# microzed_sd_v0_5_r1_1_f6faa5a5.net
KiCad netlist of a schematic drawn in EAGLE
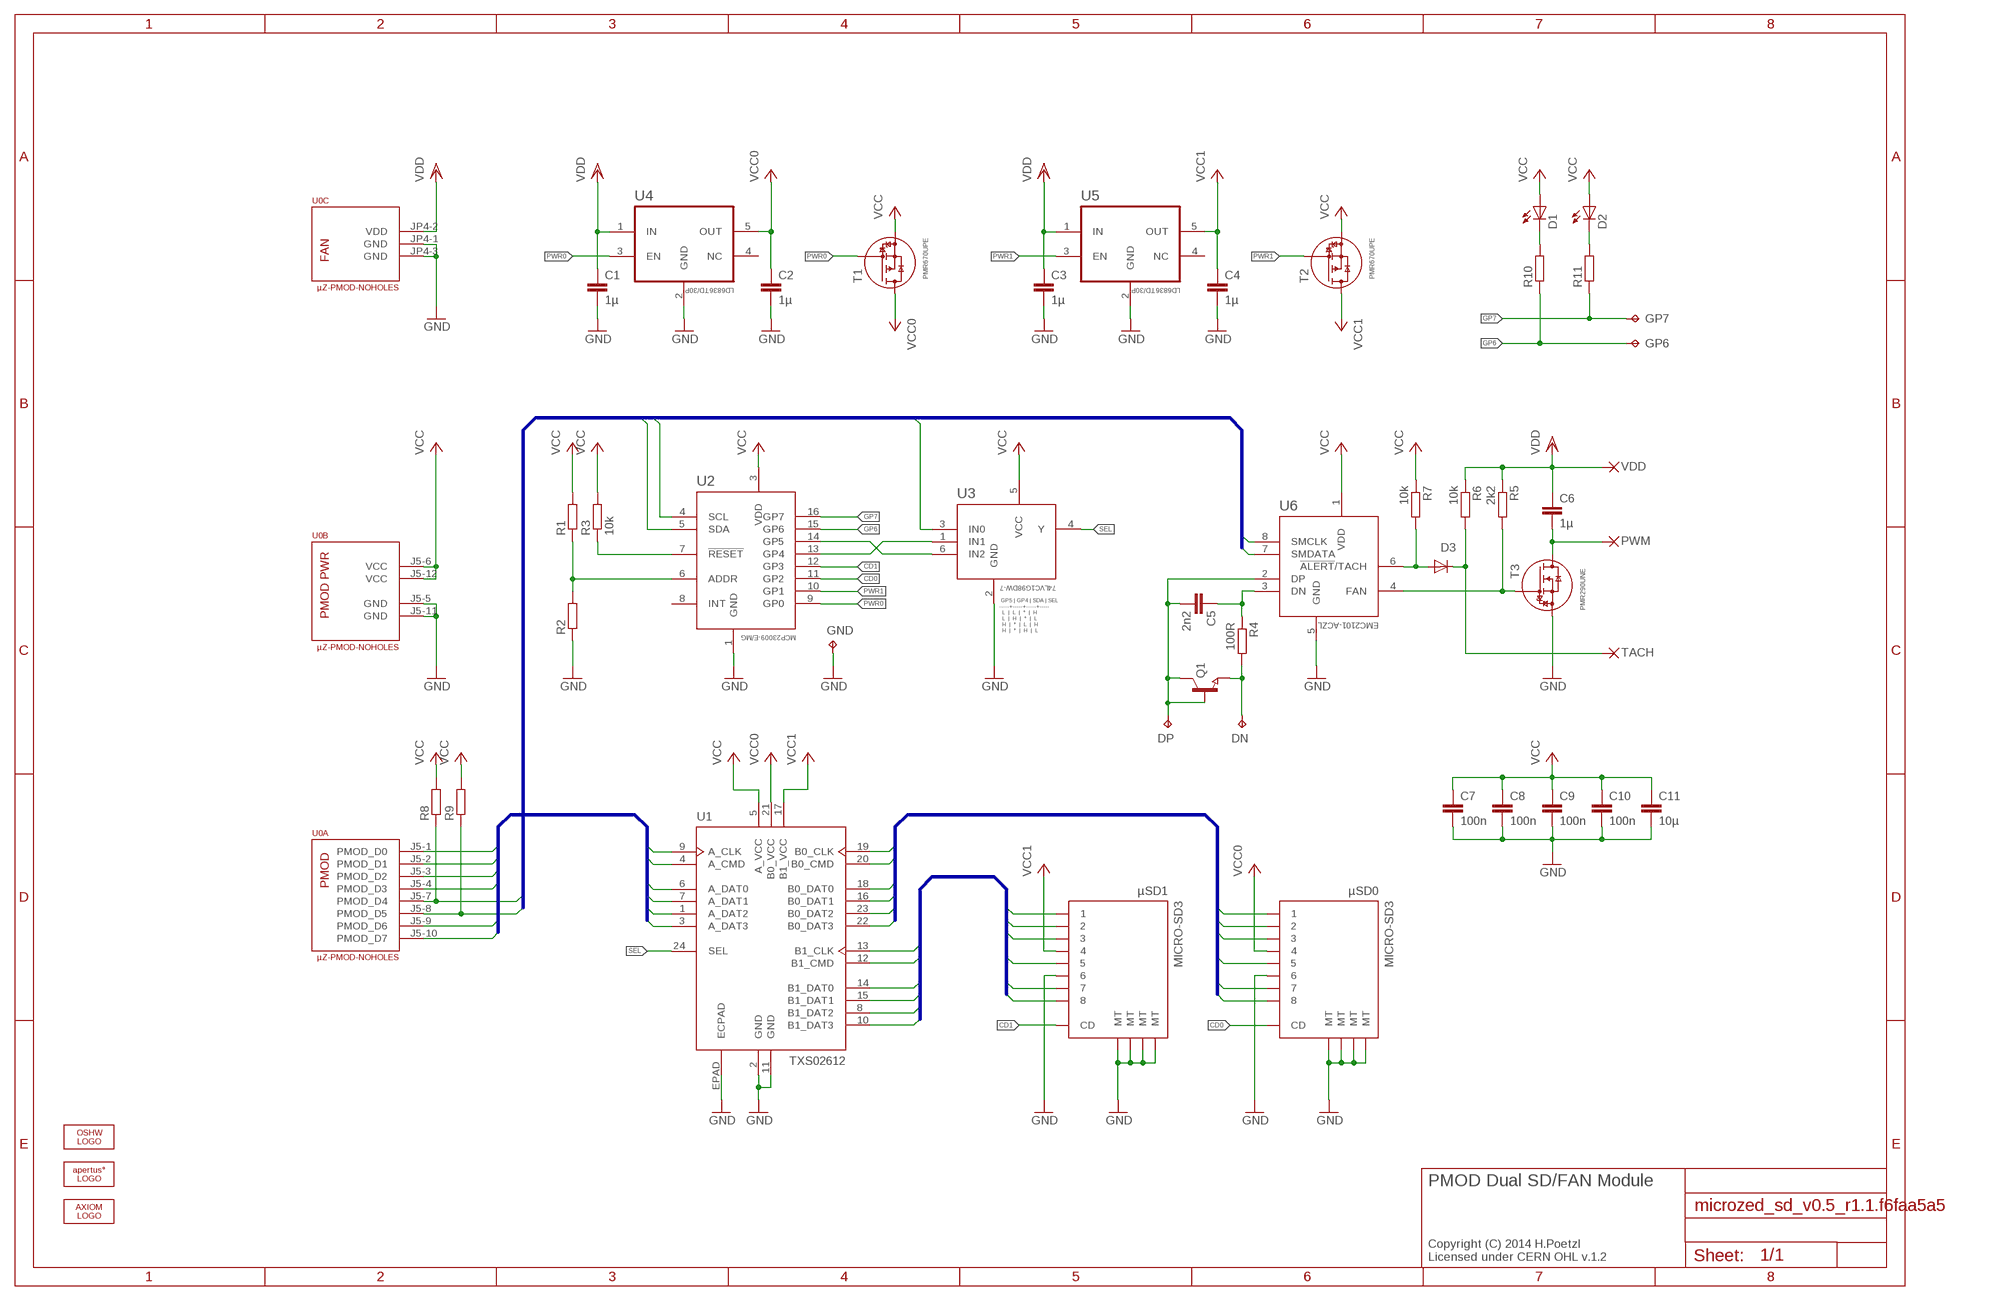
[diagram p0: schematic, sheet 1]

(export (version "E")
  (design (tool "Eeschema 10.0.6"))
  (components
    (comp (ref "C1")
      (value "1µ")
      (footprint "eagle-import:C0402K")
      (libsource (lib "eagle-import") (part "C-EUC0402K"))
    )
    (comp (ref "C2")
      (value "1µ")
      (footprint "eagle-import:C0402K")
      (libsource (lib "eagle-import") (part "C-EUC0402K"))
    )
    (comp (ref "C3")
      (value "1µ")
      (footprint "eagle-import:C0402K")
      (libsource (lib "eagle-import") (part "C-EUC0402K"))
    )
    (comp (ref "C4")
      (value "1µ")
      (footprint "eagle-import:C0402K")
      (libsource (lib "eagle-import") (part "C-EUC0402K"))
    )
    (comp (ref "C5")
      (value "2n2")
      (footprint "eagle-import:C0402K")
      (libsource (lib "eagle-import") (part "C-EUC0402K"))
    )
    (comp (ref "C6")
      (value "1µ")
      (footprint "eagle-import:C0402K")
      (libsource (lib "eagle-import") (part "C-EUC0402K"))
    )
    (comp (ref "C7")
      (value "100n")
      (footprint "eagle-import:C0402K")
      (libsource (lib "eagle-import") (part "C-EUC0402K"))
    )
    (comp (ref "C8")
      (value "100n")
      (footprint "eagle-import:C0402K")
      (libsource (lib "eagle-import") (part "C-EUC0402K"))
    )
    (comp (ref "C9")
      (value "100n")
      (footprint "eagle-import:C0402K")
      (libsource (lib "eagle-import") (part "C-EUC0402K"))
    )
    (comp (ref "C10")
      (value "100n")
      (footprint "eagle-import:C0402K")
      (libsource (lib "eagle-import") (part "C-EUC0402K"))
    )
    (comp (ref "C11")
      (value "10µ")
      (footprint "eagle-import:C0603K")
      (libsource (lib "eagle-import") (part "C-EUC0603K"))
    )
    (comp (ref "D1")
      (value "LEDCHIPLED_0603")
      (footprint "eagle-import:CHIPLED_0603")
      (libsource (lib "eagle-import") (part "LEDCHIPLED_0603"))
    )
    (comp (ref "D2")
      (value "LEDCHIPLED_0603")
      (footprint "eagle-import:CHIPLED_0603")
      (libsource (lib "eagle-import") (part "LEDCHIPLED_0603"))
    )
    (comp (ref "D3")
      (value "DIODE-MICROMELF-W")
      (footprint "eagle-import:MICROMELF-W")
      (libsource (lib "eagle-import") (part "DIODE-MICROMELF-W"))
    )
    (comp (ref "DN")
      (value "TPTP20R")
      (footprint "eagle-import:TP20R")
      (libsource (lib "eagle-import") (part "TPTP20R"))
    )
    (comp (ref "DP")
      (value "TPTP20R")
      (footprint "eagle-import:TP20R")
      (libsource (lib "eagle-import") (part "TPTP20R"))
    )
    (comp (ref "GND")
      (value "TPTP20R")
      (footprint "eagle-import:TP20R")
      (libsource (lib "eagle-import") (part "TPTP20R"))
    )
    (comp (ref "GP6")
      (value "TPTP20R")
      (footprint "eagle-import:TP20R")
      (libsource (lib "eagle-import") (part "TPTP20R"))
    )
    (comp (ref "GP7")
      (value "TPTP20R")
      (footprint "eagle-import:TP20R")
      (libsource (lib "eagle-import") (part "TPTP20R"))
    )
    (comp (ref "LOGO1")
      (value "OSHW_LOGO_FILLX0100-NT")
      (footprint "eagle-import:OSHW_FILLX100_NOTEXT")
      (libsource (lib "eagle-import") (part "OSHW_LOGO_FILLX0100-NT"))
    )
    (comp (ref "PWM")
      (value "WIREPAD1,85/1,0_SQ")
      (footprint "eagle-import:1,85_1,0_SQ")
      (libsource (lib "eagle-import") (part "WIREPAD1,85/1,0_SQ"))
    )
    (comp (ref "Q1")
      (value "NPN-TRANSISTOR_SOT23")
      (footprint "eagle-import:SOT23")
      (libsource (lib "eagle-import") (part "NPN-TRANSISTOR_SOT23"))
    )
    (comp (ref "R1")
      (value "R-EU_R0402")
      (footprint "eagle-import:R0402")
      (libsource (lib "eagle-import") (part "R-EU_R0402"))
    )
    (comp (ref "R2")
      (value "R-EU_R0402")
      (footprint "eagle-import:R0402")
      (libsource (lib "eagle-import") (part "R-EU_R0402"))
    )
    (comp (ref "R3")
      (value "10k")
      (footprint "eagle-import:R0402")
      (libsource (lib "eagle-import") (part "R-EU_R0402"))
    )
    (comp (ref "R4")
      (value "100R")
      (footprint "eagle-import:R0402")
      (libsource (lib "eagle-import") (part "R-EU_R0402"))
    )
    (comp (ref "R5")
      (value "2k2")
      (footprint "eagle-import:R0402")
      (libsource (lib "eagle-import") (part "R-EU_R0402"))
    )
    (comp (ref "R6")
      (value "10k")
      (footprint "eagle-import:R0402")
      (libsource (lib "eagle-import") (part "R-EU_R0402"))
    )
    (comp (ref "R7")
      (value "10k")
      (footprint "eagle-import:R0402")
      (libsource (lib "eagle-import") (part "R-EU_R0402"))
    )
    (comp (ref "R8")
      (value "R-EU_R0402")
      (footprint "eagle-import:R0402")
      (libsource (lib "eagle-import") (part "R-EU_R0402"))
    )
    (comp (ref "R9")
      (value "R-EU_R0402")
      (footprint "eagle-import:R0402")
      (libsource (lib "eagle-import") (part "R-EU_R0402"))
    )
    (comp (ref "R10")
      (value "R-EU_R0402")
      (footprint "eagle-import:R0402")
      (libsource (lib "eagle-import") (part "R-EU_R0402"))
    )
    (comp (ref "R11")
      (value "R-EU_R0402")
      (footprint "eagle-import:R0402")
      (libsource (lib "eagle-import") (part "R-EU_R0402"))
    )
    (comp (ref "T1")
      (value "PMR670UPE")
      (footprint "eagle-import:SOT416")
      (libsource (lib "eagle-import") (part "PMR670UPE"))
    )
    (comp (ref "T2")
      (value "PMR670UPE")
      (footprint "eagle-import:SOT416")
      (libsource (lib "eagle-import") (part "PMR670UPE"))
    )
    (comp (ref "T3")
      (value "PMR290UNE")
      (footprint "eagle-import:SOT416")
      (libsource (lib "eagle-import") (part "PMR290UNE"))
    )
    (comp (ref "TACH")
      (value "WIREPAD1,85/1,0")
      (footprint "eagle-import:1,85_1,0")
      (libsource (lib "eagle-import") (part "WIREPAD1,85/1,0"))
    )
    (comp (ref "U$1")
      (value "APERTUS_LOGO334X100")
      (footprint "eagle-import:APERTUS_LOGO_334X100")
      (libsource (lib "eagle-import") (part "APERTUS_LOGO334X100"))
    )
    (comp (ref "U$13")
      (value "AXIOM_LOGO525X80")
      (footprint "eagle-import:AXIOM_LOGO_525X80")
      (libsource (lib "eagle-import") (part "AXIOM_LOGO525X80"))
    )
    (comp (ref "U0")
      (value "µZ-PMOD-NOHOLES")
      (footprint "eagle-import:µZ-TOP-NOHOLES")
      (libsource (lib "eagle-import") (part "µZ-PMOD-NOHOLES"))
    )
    (comp (ref "U1")
      (value "TXS02612")
      (footprint "eagle-import:S-PWQFN-N24")
      (libsource (lib "eagle-import") (part "TXS02612"))
    )
    (comp (ref "U2")
      (value "MCP23009-E/MG")
      (footprint "eagle-import:QFN50P300X300X80-17N")
      (libsource (lib "eagle-import") (part "MCP23009-E/MG"))
    )
    (comp (ref "U3")
      (value "74LVC1G98DW-7")
      (footprint "eagle-import:SOT65P210X110-6N")
      (libsource (lib "eagle-import") (part "74LVC1G98DW-7"))
    )
    (comp (ref "U4")
      (value "LD6836TD/30P")
      (footprint "eagle-import:SOT95P275X110-5N")
      (libsource (lib "eagle-import") (part "LD6836TD/30P"))
    )
    (comp (ref "U5")
      (value "LD6836TD/30P")
      (footprint "eagle-import:SOT95P275X110-5N")
      (libsource (lib "eagle-import") (part "LD6836TD/30P"))
    )
    (comp (ref "U6")
      (value "EMC2101-ACZL")
      (footprint "eagle-import:SOP65P490X110-8N")
      (fields (field (name "MPN") "EMC2101-ACZL-TR "))
      (libsource (lib "eagle-import") (part "EMC2101-ACZL"))
    )
    (comp (ref "VDD")
      (value "WIREPAD1,85/1,0")
      (footprint "eagle-import:1,85_1,0")
      (libsource (lib "eagle-import") (part "WIREPAD1,85/1,0"))
    )
    (comp (ref "µSD0")
      (value "MICRO-SD3")
      (footprint "eagle-import:TF-MICRO-SD_PP3")
      (libsource (lib "eagle-import") (part "MICRO-SD3"))
    )
    (comp (ref "µSD1")
      (value "MICRO-SD3")
      (footprint "eagle-import:TF-MICRO-SD_PP3")
      (libsource (lib "eagle-import") (part "MICRO-SD3"))
    )
  )
  (nets
    (net (code "1") (name "/A_CLK") (class "Default")
      (node (ref "U0") (pin "J5-4") (pinfunction "PMOD_D3_J5-4") (pintype "bidirectional"))
      (node (ref "U1") (pin "9") (pinfunction "A_CLK_9") (pintype "input"))
    )
    (net (code "2") (name "/A_CMD") (class "Default")
      (node (ref "U0") (pin "J5-3") (pinfunction "PMOD_D2_J5-3") (pintype "bidirectional"))
      (node (ref "U1") (pin "4") (pinfunction "A_CMD_4") (pintype "bidirectional"))
    )
    (net (code "3") (name "/A_DAT0") (class "Default")
      (node (ref "U0") (pin "J5-2") (pinfunction "PMOD_D1_J5-2") (pintype "bidirectional"))
      (node (ref "U1") (pin "6") (pinfunction "A_DAT0_6") (pintype "bidirectional"))
    )
    (net (code "4") (name "/A_DAT1") (class "Default")
      (node (ref "U0") (pin "J5-1") (pinfunction "PMOD_D0_J5-1") (pintype "bidirectional"))
      (node (ref "U1") (pin "7") (pinfunction "A_DAT1_7") (pintype "bidirectional"))
    )
    (net (code "5") (name "/A_DAT2") (class "Default")
      (node (ref "U0") (pin "J5-9") (pinfunction "PMOD_D6_J5-9") (pintype "bidirectional"))
      (node (ref "U1") (pin "1") (pinfunction "A_DAT2_1") (pintype "bidirectional"))
    )
    (net (code "6") (name "/A_DAT3") (class "Default")
      (node (ref "U0") (pin "J5-10") (pinfunction "PMOD_D7_J5-10") (pintype "bidirectional"))
      (node (ref "U1") (pin "3") (pinfunction "A_DAT3_3") (pintype "bidirectional"))
    )
    (net (code "7") (name "/B0_CLK") (class "Default")
      (node (ref "U1") (pin "19") (pinfunction "B0_CLK_19") (pintype "output"))
      (node (ref "µSD0") (pin "5") (pinfunction "5_5") (pintype "bidirectional"))
    )
    (net (code "8") (name "/B0_CMD") (class "Default")
      (node (ref "U1") (pin "20") (pinfunction "B0_CMD_20") (pintype "bidirectional"))
      (node (ref "µSD0") (pin "3") (pinfunction "3_3") (pintype "bidirectional"))
    )
    (net (code "9") (name "/B0_DAT0") (class "Default")
      (node (ref "U1") (pin "18") (pinfunction "B0_DAT0_18") (pintype "bidirectional"))
      (node (ref "µSD0") (pin "7") (pinfunction "7_7") (pintype "bidirectional"))
    )
    (net (code "10") (name "/B0_DAT1") (class "Default")
      (node (ref "U1") (pin "16") (pinfunction "B0_DAT1_16") (pintype "bidirectional"))
      (node (ref "µSD0") (pin "8") (pinfunction "8_8") (pintype "bidirectional"))
    )
    (net (code "11") (name "/B0_DAT2") (class "Default")
      (node (ref "U1") (pin "23") (pinfunction "B0_DAT2_23") (pintype "bidirectional"))
      (node (ref "µSD0") (pin "1") (pinfunction "1_1") (pintype "bidirectional"))
    )
    (net (code "12") (name "/B0_DAT3") (class "Default")
      (node (ref "U1") (pin "22") (pinfunction "B0_DAT3_22") (pintype "bidirectional"))
      (node (ref "µSD0") (pin "2") (pinfunction "2_2") (pintype "bidirectional"))
    )
    (net (code "13") (name "/B1_CLK") (class "Default")
      (node (ref "U1") (pin "13") (pinfunction "B1_CLK_13") (pintype "output"))
      (node (ref "µSD1") (pin "5") (pinfunction "5_5") (pintype "bidirectional"))
    )
    (net (code "14") (name "/B1_CMD") (class "Default")
      (node (ref "U1") (pin "12") (pinfunction "B1_CMD_12") (pintype "bidirectional"))
      (node (ref "µSD1") (pin "3") (pinfunction "3_3") (pintype "bidirectional"))
    )
    (net (code "15") (name "/B1_DAT0") (class "Default")
      (node (ref "U1") (pin "14") (pinfunction "B1_DAT0_14") (pintype "bidirectional"))
      (node (ref "µSD1") (pin "7") (pinfunction "7_7") (pintype "bidirectional"))
    )
    (net (code "16") (name "/B1_DAT1") (class "Default")
      (node (ref "U1") (pin "15") (pinfunction "B1_DAT1_15") (pintype "bidirectional"))
      (node (ref "µSD1") (pin "8") (pinfunction "8_8") (pintype "bidirectional"))
    )
    (net (code "17") (name "/B1_DAT2") (class "Default")
      (node (ref "U1") (pin "8") (pinfunction "B1_DAT2_8") (pintype "bidirectional"))
      (node (ref "µSD1") (pin "1") (pinfunction "1_1") (pintype "bidirectional"))
    )
    (net (code "18") (name "/B1_DAT3") (class "Default")
      (node (ref "U1") (pin "10") (pinfunction "B1_DAT3_10") (pintype "bidirectional"))
      (node (ref "µSD1") (pin "2") (pinfunction "2_2") (pintype "bidirectional"))
    )
    (net (code "19") (name "/SCL") (class "Default")
      (node (ref "R8") (pin "1") (pinfunction "1_1") (pintype "passive"))
      (node (ref "U0") (pin "J5-7") (pinfunction "PMOD_D4_J5-7") (pintype "bidirectional"))
      (node (ref "U2") (pin "4") (pinfunction "SCL_4") (pintype "input"))
      (node (ref "U6") (pin "8") (pinfunction "SMCLK_8") (pintype "input"))
    )
    (net (code "20") (name "/SDA") (class "Default")
      (node (ref "R9") (pin "1") (pinfunction "1_1") (pintype "passive"))
      (node (ref "U0") (pin "J5-8") (pinfunction "PMOD_D5_J5-8") (pintype "bidirectional"))
      (node (ref "U2") (pin "5") (pinfunction "SDA_5") (pintype "bidirectional"))
      (node (ref "U3") (pin "3") (pinfunction "IN0_3") (pintype "input"))
      (node (ref "U6") (pin "7") (pinfunction "SMDATA_7") (pintype "bidirectional"))
    )
    (net (code "21") (name "CD0") (class "Default")
      (node (ref "U2") (pin "11") (pinfunction "GP2_11") (pintype "bidirectional"))
      (node (ref "µSD0") (pin "CD") (pinfunction "CD_CD") (pintype "bidirectional"))
    )
    (net (code "22") (name "CD1") (class "Default")
      (node (ref "U2") (pin "12") (pinfunction "GP3_12") (pintype "bidirectional"))
      (node (ref "µSD1") (pin "CD") (pinfunction "CD_CD") (pintype "bidirectional"))
    )
    (net (code "23") (name "GND") (class "Default")
      (node (ref "C1") (pin "2") (pinfunction "2_2") (pintype "passive"))
      (node (ref "C10") (pin "2") (pinfunction "2_2") (pintype "passive"))
      (node (ref "C11") (pin "2") (pinfunction "2_2") (pintype "passive"))
      (node (ref "C2") (pin "2") (pinfunction "2_2") (pintype "passive"))
      (node (ref "C3") (pin "2") (pinfunction "2_2") (pintype "passive"))
      (node (ref "C4") (pin "2") (pinfunction "2_2") (pintype "passive"))
      (node (ref "C7") (pin "2") (pinfunction "2_2") (pintype "passive"))
      (node (ref "C8") (pin "2") (pinfunction "2_2") (pintype "passive"))
      (node (ref "C9") (pin "2") (pinfunction "2_2") (pintype "passive"))
      (node (ref "GND") (pin "TP") (pinfunction "TP_TP") (pintype "input"))
      (node (ref "R2") (pin "1") (pinfunction "1_1") (pintype "passive"))
      (node (ref "T3") (pin "2") (pinfunction "S_2") (pintype "passive"))
      (node (ref "U0") (pin "J5-11") (pinfunction "GND_J5-11") (pintype "power_in"))
      (node (ref "U0") (pin "J5-5") (pinfunction "GND_J5-5") (pintype "power_in"))
      (node (ref "U0") (pin "JP4-1") (pinfunction "GND_JP4-1") (pintype "power_in"))
      (node (ref "U0") (pin "JP4-3") (pinfunction "GND_JP4-3") (pintype "power_in"))
      (node (ref "U1") (pin "11") (pinfunction "GND_11") (pintype "power_in"))
      (node (ref "U1") (pin "2") (pinfunction "GND_2") (pintype "power_in"))
      (node (ref "U1") (pin "EPAD") (pinfunction "ECPAD_EPAD") (pintype "power_in"))
      (node (ref "U2") (pin "1") (pinfunction "GND_1") (pintype "power_in"))
      (node (ref "U3") (pin "2") (pinfunction "GND_2") (pintype "passive"))
      (node (ref "U4") (pin "2") (pinfunction "GND_2") (pintype "passive"))
      (node (ref "U5") (pin "2") (pinfunction "GND_2") (pintype "passive"))
      (node (ref "U6") (pin "5") (pinfunction "GND_5") (pintype "power_in"))
      (node (ref "µSD0") (pin "6") (pinfunction "6_6") (pintype "bidirectional"))
      (node (ref "µSD0") (pin "MT1") (pinfunction "MT_MT1") (pintype "power_in"))
      (node (ref "µSD0") (pin "MT2") (pinfunction "MT_MT2") (pintype "power_in"))
      (node (ref "µSD0") (pin "MT3") (pinfunction "MT_MT3") (pintype "power_in"))
      (node (ref "µSD0") (pin "MT4") (pinfunction "MT_MT4") (pintype "power_in"))
      (node (ref "µSD1") (pin "6") (pinfunction "6_6") (pintype "bidirectional"))
      (node (ref "µSD1") (pin "MT1") (pinfunction "MT_MT1") (pintype "power_in"))
      (node (ref "µSD1") (pin "MT2") (pinfunction "MT_MT2") (pintype "power_in"))
      (node (ref "µSD1") (pin "MT3") (pinfunction "MT_MT3") (pintype "power_in"))
      (node (ref "µSD1") (pin "MT4") (pinfunction "MT_MT4") (pintype "power_in"))
    )
    (net (code "24") (name "GP6") (class "Default")
      (node (ref "GP6") (pin "TP") (pinfunction "TP_TP") (pintype "input"))
      (node (ref "R10") (pin "1") (pinfunction "1_1") (pintype "passive"))
      (node (ref "U2") (pin "15") (pinfunction "GP6_15") (pintype "bidirectional"))
    )
    (net (code "25") (name "GP7") (class "Default")
      (node (ref "GP7") (pin "TP") (pinfunction "TP_TP") (pintype "input"))
      (node (ref "R11") (pin "1") (pinfunction "1_1") (pintype "passive"))
      (node (ref "U2") (pin "16") (pinfunction "GP7_16") (pintype "bidirectional"))
    )
    (net (code "26") (name "Net-(D1-PadC)") (class "Default")
      (node (ref "D1") (pin "C") (pinfunction "C_C") (pintype "passive"))
      (node (ref "R10") (pin "2") (pinfunction "2_2") (pintype "passive"))
    )
    (net (code "27") (name "Net-(D2-PadC)") (class "Default")
      (node (ref "D2") (pin "C") (pinfunction "C_C") (pintype "passive"))
      (node (ref "R11") (pin "2") (pinfunction "2_2") (pintype "passive"))
    )
    (net (code "28") (name "Net-(PWM-P)") (class "Default")
      (node (ref "C6") (pin "2") (pinfunction "2_2") (pintype "passive"))
      (node (ref "PWM") (pin "1") (pinfunction "P_1") (pintype "passive"))
      (node (ref "T3") (pin "3") (pinfunction "D_3") (pintype "passive"))
    )
    (net (code "29") (name "Net-(Q1-B)") (class "Default")
      (node (ref "C5") (pin "2") (pinfunction "2_2") (pintype "passive"))
      (node (ref "DP") (pin "TP") (pinfunction "TP_TP") (pintype "input"))
      (node (ref "Q1") (pin "1") (pinfunction "B_1") (pintype "passive"))
      (node (ref "Q1") (pin "3") (pinfunction "C_3") (pintype "passive"))
      (node (ref "U6") (pin "2") (pinfunction "DP_2") (pintype "passive"))
    )
    (net (code "30") (name "Net-(Q1-E)") (class "Default")
      (node (ref "DN") (pin "TP") (pinfunction "TP_TP") (pintype "input"))
      (node (ref "Q1") (pin "2") (pinfunction "E_2") (pintype "passive"))
      (node (ref "R4") (pin "2") (pinfunction "2_2") (pintype "passive"))
    )
    (net (code "31") (name "Net-(T3-G)") (class "Default")
      (node (ref "R5") (pin "2") (pinfunction "2_2") (pintype "passive"))
      (node (ref "T3") (pin "1") (pinfunction "G_1") (pintype "passive"))
      (node (ref "U6") (pin "4") (pinfunction "FAN_4") (pintype "output"))
    )
    (net (code "32") (name "Net-(TACH-P)") (class "Default")
      (node (ref "D3") (pin "C") (pinfunction "C_C") (pintype "passive"))
      (node (ref "R6") (pin "2") (pinfunction "2_2") (pintype "passive"))
      (node (ref "TACH") (pin "1") (pinfunction "P_1") (pintype "passive"))
    )
    (net (code "33") (name "Net-(U2-ADDR)") (class "Default")
      (node (ref "R1") (pin "1") (pinfunction "1_1") (pintype "passive"))
      (node (ref "R2") (pin "2") (pinfunction "2_2") (pintype "passive"))
      (node (ref "U2") (pin "6") (pinfunction "ADDR_6") (pintype "input"))
    )
    (net (code "34") (name "Net-(U2-GP4)") (class "Default")
      (node (ref "U2") (pin "13") (pinfunction "GP4_13") (pintype "bidirectional"))
      (node (ref "U3") (pin "1") (pinfunction "IN1_1") (pintype "input"))
    )
    (net (code "35") (name "Net-(U2-GP5)") (class "Default")
      (node (ref "U2") (pin "14") (pinfunction "GP5_14") (pintype "bidirectional"))
      (node (ref "U3") (pin "6") (pinfunction "IN2_6") (pintype "input"))
    )
    (net (code "36") (name "Net-(U2-~{RESET})") (class "Default")
      (node (ref "R3") (pin "1") (pinfunction "1_1") (pintype "passive"))
      (node (ref "U2") (pin "7") (pinfunction "~{RESET}_7") (pintype "input"))
    )
    (net (code "37") (name "Net-(U6-DN)") (class "Default")
      (node (ref "C5") (pin "1") (pinfunction "1_1") (pintype "passive"))
      (node (ref "R4") (pin "1") (pinfunction "1_1") (pintype "passive"))
      (node (ref "U6") (pin "3") (pinfunction "DN_3") (pintype "passive"))
    )
    (net (code "38") (name "Net-(U6-~{ALERT}{slash}TACH)") (class "Default")
      (node (ref "D3") (pin "A") (pinfunction "A_A") (pintype "passive"))
      (node (ref "R7") (pin "2") (pinfunction "2_2") (pintype "passive"))
      (node (ref "U6") (pin "6") (pinfunction "~{ALERT}/TACH_6") (pintype "bidirectional"))
    )
    (net (code "39") (name "PWR0") (class "Default")
      (node (ref "T1") (pin "1") (pinfunction "G_1") (pintype "passive"))
      (node (ref "U2") (pin "9") (pinfunction "GP0_9") (pintype "bidirectional"))
      (node (ref "U4") (pin "3") (pinfunction "EN_3") (pintype "input"))
    )
    (net (code "40") (name "PWR1") (class "Default")
      (node (ref "T2") (pin "1") (pinfunction "G_1") (pintype "passive"))
      (node (ref "U2") (pin "10") (pinfunction "GP1_10") (pintype "bidirectional"))
      (node (ref "U5") (pin "3") (pinfunction "EN_3") (pintype "input"))
    )
    (net (code "41") (name "SEL") (class "Default")
      (node (ref "U1") (pin "24") (pinfunction "SEL_24") (pintype "input"))
      (node (ref "U3") (pin "4") (pinfunction "Y_4") (pintype "output"))
    )
    (net (code "42") (name "VCC") (class "Default")
      (node (ref "C10") (pin "1") (pinfunction "1_1") (pintype "passive"))
      (node (ref "C11") (pin "1") (pinfunction "1_1") (pintype "passive"))
      (node (ref "C7") (pin "1") (pinfunction "1_1") (pintype "passive"))
      (node (ref "C8") (pin "1") (pinfunction "1_1") (pintype "passive"))
      (node (ref "C9") (pin "1") (pinfunction "1_1") (pintype "passive"))
      (node (ref "D1") (pin "A") (pinfunction "A_A") (pintype "passive"))
      (node (ref "D2") (pin "A") (pinfunction "A_A") (pintype "passive"))
      (node (ref "R1") (pin "2") (pinfunction "2_2") (pintype "passive"))
      (node (ref "R3") (pin "2") (pinfunction "2_2") (pintype "passive"))
      (node (ref "R7") (pin "1") (pinfunction "1_1") (pintype "passive"))
      (node (ref "R8") (pin "2") (pinfunction "2_2") (pintype "passive"))
      (node (ref "R9") (pin "2") (pinfunction "2_2") (pintype "passive"))
      (node (ref "T1") (pin "2") (pinfunction "S_2") (pintype "passive"))
      (node (ref "T2") (pin "2") (pinfunction "S_2") (pintype "passive"))
      (node (ref "U0") (pin "J5-12") (pinfunction "VCC_J5-12") (pintype "power_in"))
      (node (ref "U0") (pin "J5-6") (pinfunction "VCC_J5-6") (pintype "power_in"))
      (node (ref "U1") (pin "5") (pinfunction "A_VCC_5") (pintype "power_in"))
      (node (ref "U2") (pin "3") (pinfunction "VDD_3") (pintype "power_in"))
      (node (ref "U3") (pin "5") (pinfunction "VCC_5") (pintype "power_in"))
      (node (ref "U6") (pin "1") (pinfunction "VDD_1") (pintype "power_in"))
    )
    (net (code "43") (name "VCC0") (class "Default")
      (node (ref "C2") (pin "1") (pinfunction "1_1") (pintype "passive"))
      (node (ref "T1") (pin "3") (pinfunction "D_3") (pintype "passive"))
      (node (ref "U1") (pin "21") (pinfunction "B0_VCC_21") (pintype "power_in"))
      (node (ref "U4") (pin "5") (pinfunction "OUT_5") (pintype "output"))
      (node (ref "µSD0") (pin "4") (pinfunction "4_4") (pintype "bidirectional"))
    )
    (net (code "44") (name "VCC1") (class "Default")
      (node (ref "C4") (pin "1") (pinfunction "1_1") (pintype "passive"))
      (node (ref "T2") (pin "3") (pinfunction "D_3") (pintype "passive"))
      (node (ref "U1") (pin "17") (pinfunction "B1_VCC_17") (pintype "power_in"))
      (node (ref "U5") (pin "5") (pinfunction "OUT_5") (pintype "output"))
      (node (ref "µSD1") (pin "4") (pinfunction "4_4") (pintype "bidirectional"))
    )
    (net (code "45") (name "VDD") (class "Default")
      (node (ref "C1") (pin "1") (pinfunction "1_1") (pintype "passive"))
      (node (ref "C3") (pin "1") (pinfunction "1_1") (pintype "passive"))
      (node (ref "C6") (pin "1") (pinfunction "1_1") (pintype "passive"))
      (node (ref "R5") (pin "1") (pinfunction "1_1") (pintype "passive"))
      (node (ref "R6") (pin "1") (pinfunction "1_1") (pintype "passive"))
      (node (ref "U0") (pin "JP4-2") (pinfunction "VDD_JP4-2") (pintype "power_in"))
      (node (ref "U4") (pin "1") (pinfunction "IN_1") (pintype "input"))
      (node (ref "U5") (pin "1") (pinfunction "IN_1") (pintype "input"))
      (node (ref "VDD") (pin "1") (pinfunction "P_1") (pintype "passive"))
    )
    (net (code "46") (name "unconnected-(U2-INT-Pad8)") (class "Default")
      (node (ref "U2") (pin "8") (pinfunction "INT_8") (pintype "output"))
    )
    (net (code "47") (name "unconnected-(U4-NC-Pad4)") (class "Default")
      (node (ref "U4") (pin "4") (pinfunction "NC_4") (pintype "no_connect"))
    )
    (net (code "48") (name "unconnected-(U5-NC-Pad4)") (class "Default")
      (node (ref "U5") (pin "4") (pinfunction "NC_4") (pintype "no_connect"))
    )
  )
)
